# IO_Boardv3_281215.net
KiCad netlist of a schematic drawn in Altium Designer
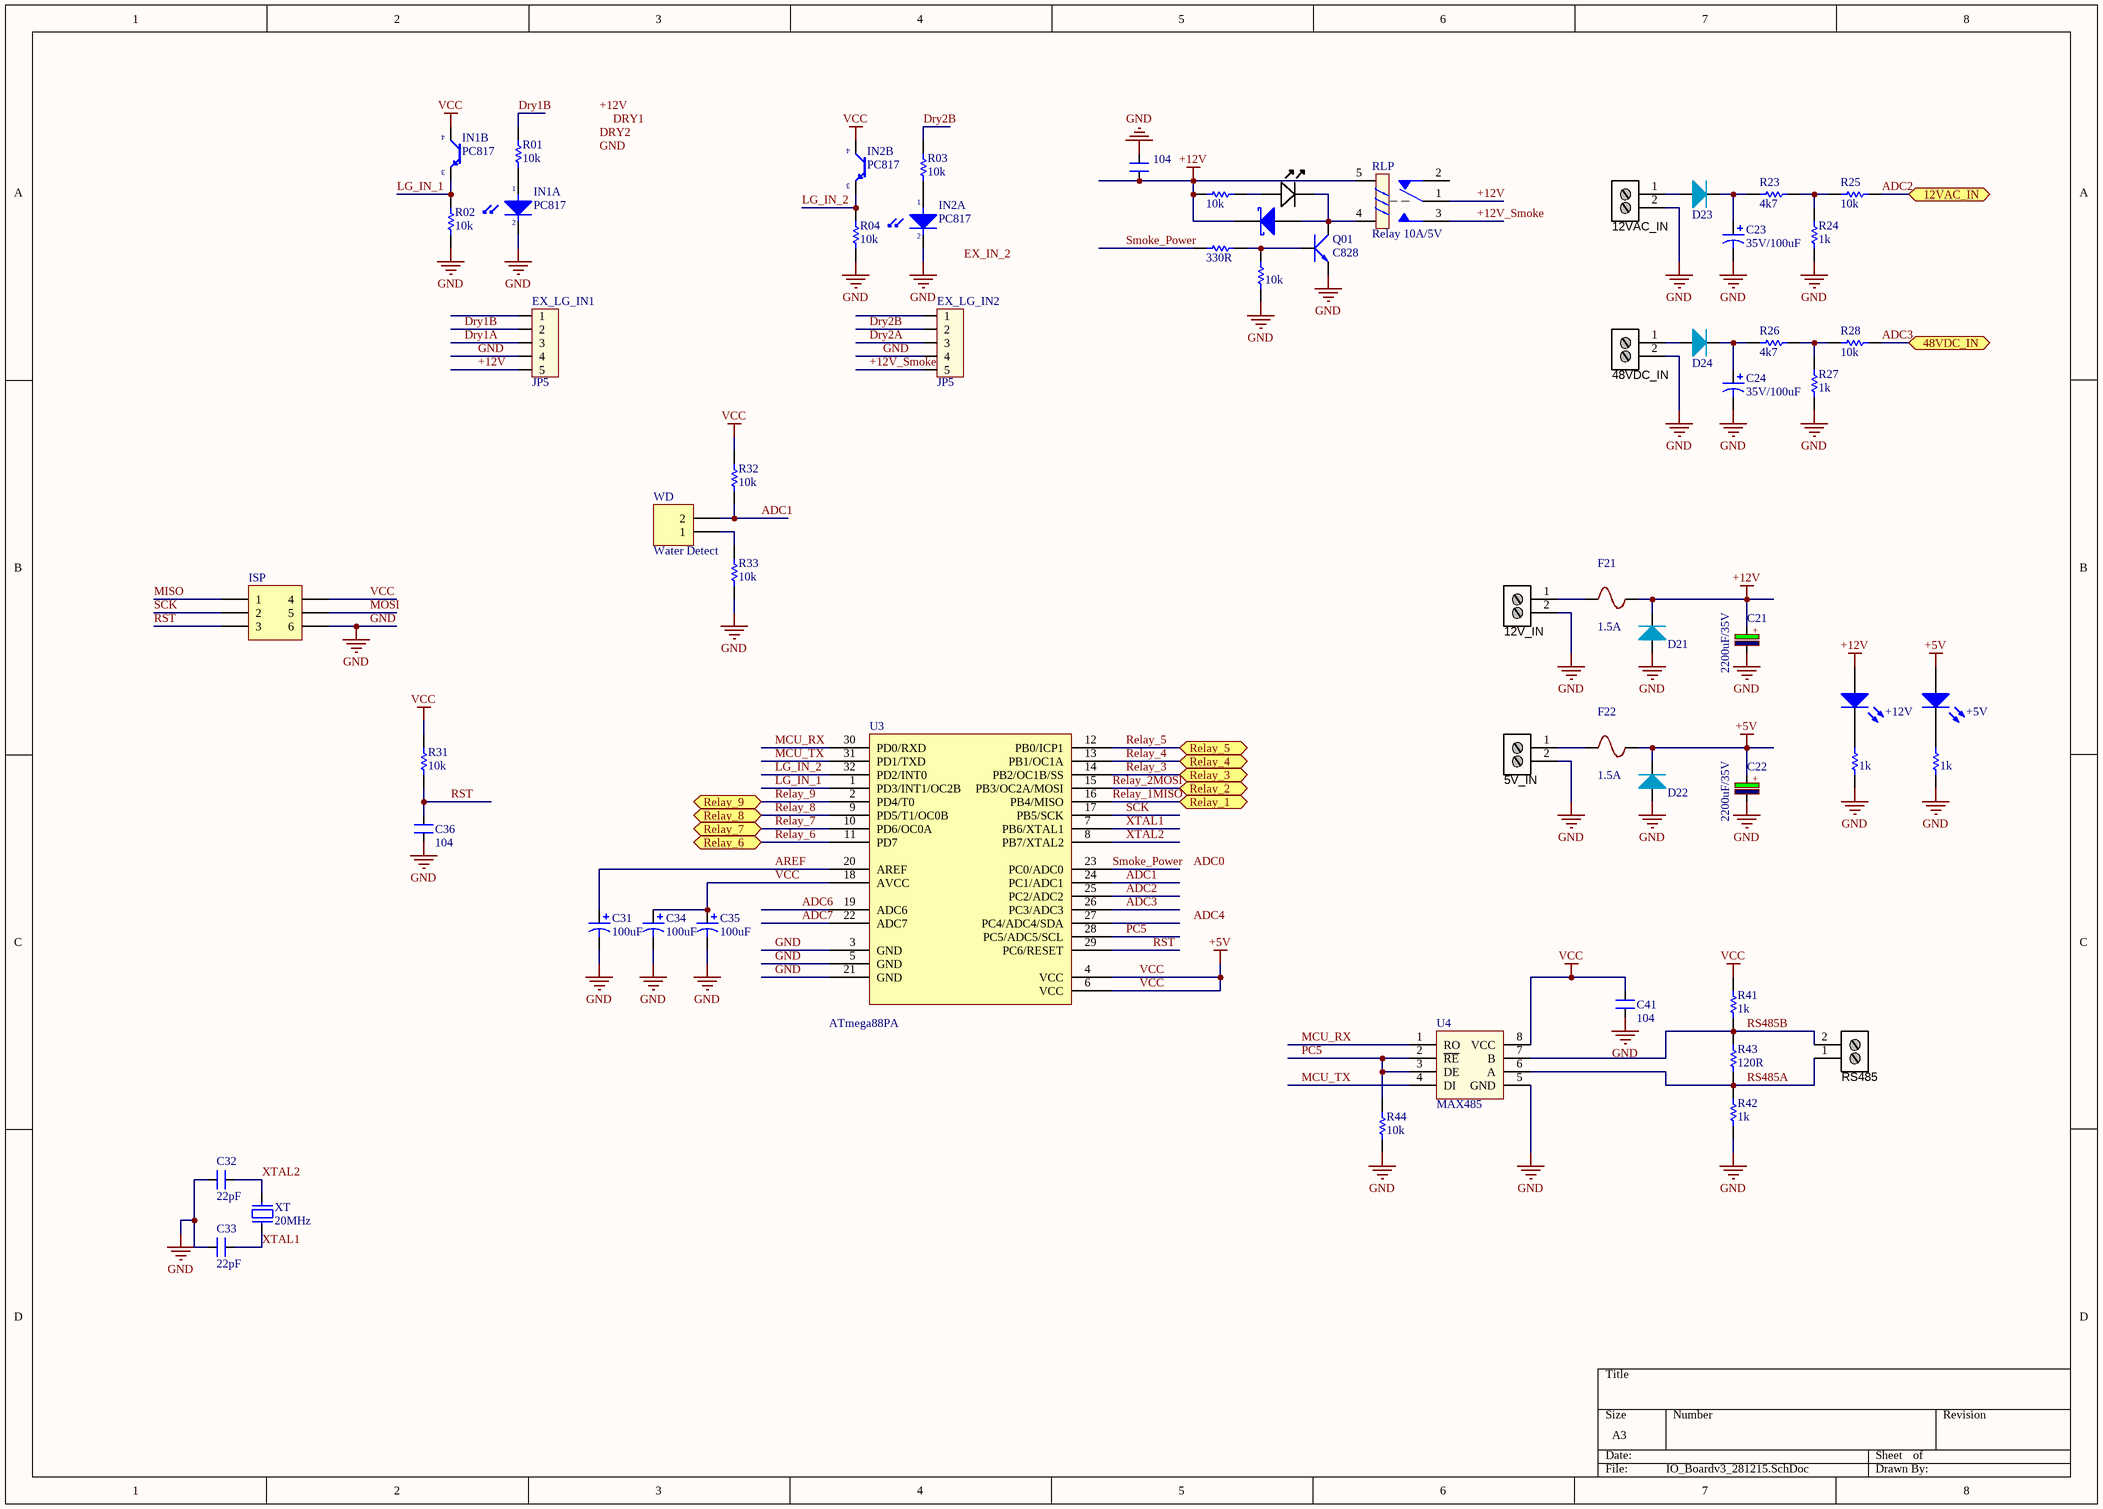
[diagram p0: IO_Boardv3_281215.SchDoc]

(export (version "E")
  (design (tool "Eeschema 10.0.6"))
  (components
    (comp (ref "+5V") (value "Led") (footprint "LED 5mm RED") (libsource (lib "Tuan") (part "Led")))
    (comp (ref "+12V") (value "Led") (footprint "LED 5mm RED") (libsource (lib "Tuan") (part "Led")))
    (comp (ref "5V_IN")
      (value "Stackable ScrewTerm")
      (footprint "2P_PCB_ScrewTerm_200mil")
      (description "Terminal Block Screw Type THT 2-Position 3.81mm pitch")
      (libsource (lib "PBL - Connectors") (part "2P_ScrewTerm_90S_3.81MM"))
    )
    (comp (ref "12VAC_IN")
      (value "Stackable ScrewTerm")
      (footprint "2P_PCB_ScrewTerm_200mil")
      (description "Terminal Block Screw Type THT 2-Position 3.81mm pitch")
      (libsource (lib "PBL - Connectors") (part "2P_ScrewTerm_90S_3.81MM"))
    )
    (comp (ref "12V_IN")
      (value "Stackable ScrewTerm")
      (footprint "2P_PCB_ScrewTerm_200mil")
      (description "Terminal Block Screw Type THT 2-Position 3.81mm pitch")
      (libsource (lib "PBL - Connectors") (part "2P_ScrewTerm_90S_3.81MM"))
    )
    (comp (ref "48VDC_IN")
      (value "Stackable ScrewTerm")
      (footprint "2P_PCB_ScrewTerm_200mil")
      (description "Terminal Block Screw Type THT 2-Position 3.81mm pitch")
      (libsource (lib "PBL - Connectors") (part "2P_ScrewTerm_90S_3.81MM"))
    )
    (comp (ref "C01")
      (value "104")
      (footprint "CAPC2012N_F")
      (fields (field (name "Comment") "CAP NP"))
      (libsource (lib "Tuan") (part "CAP NP"))
    )
    (comp (ref "C21")
      (value "2200uF/35V")
      (footprint "heromap:CP_1000uF_25V")
      (description "Cap 1000uF/16V - 220uF/50V")
      (libsource (lib "heromap") (part "CP4"))
    )
    (comp (ref "C22")
      (value "2200uF/35V")
      (footprint "heromap:CP_1000uF_25V")
      (description "Cap 1000uF/16V - 220uF/50V")
      (libsource (lib "heromap") (part "CP4"))
    )
    (comp (ref "C23")
      (value "35V/100uF")
      (footprint "CAP_ELEC_6.3x4.2")
      (fields (field (name "Comment") "Cap"))
      (libsource (lib "Tuan") (part "Cap"))
    )
    (comp (ref "C24")
      (value "35V/100uF")
      (footprint "CAP_ELEC_6.3x4.2")
      (fields (field (name "Comment") "Cap"))
      (libsource (lib "Tuan") (part "Cap"))
    )
    (comp (ref "C31")
      (value "100uF")
      (footprint "CAPC2012N_F")
      (fields (field (name "Comment") "Cap"))
      (libsource (lib "Tuan") (part "Cap"))
    )
    (comp (ref "C32")
      (value "22pF")
      (footprint "CAPC1608N")
      (fields (field (name "Comment") "CAP NP"))
      (libsource (lib "Tuan") (part "CAP NP"))
    )
    (comp (ref "C33")
      (value "22pF")
      (footprint "CAPC1608N")
      (fields (field (name "Comment") "CAP NP"))
      (libsource (lib "Tuan") (part "CAP NP"))
    )
    (comp (ref "C34")
      (value "100uF")
      (footprint "CAPC2012N_F")
      (fields (field (name "Comment") "Cap"))
      (libsource (lib "Tuan") (part "Cap"))
    )
    (comp (ref "C35")
      (value "100uF")
      (footprint "CAPC2012N_F")
      (fields (field (name "Comment") "Cap"))
      (libsource (lib "Tuan") (part "Cap"))
    )
    (comp (ref "C36")
      (value "104")
      (footprint "CAPC1608N")
      (fields (field (name "Comment") "CAP NP"))
      (libsource (lib "Tuan") (part "CAP NP"))
    )
    (comp (ref "C41")
      (value "104")
      (footprint "CAPC2012N_F")
      (fields (field (name "Comment") "100nF/104"))
      (libsource (lib "Tuan") (part "CAP NP"))
    )
    (comp (ref "D01") (value "Diode") (footprint "DO-214AC") (libsource (lib "") (part "Diode_1")))
    (comp (ref "D21") (value "Diode") (footprint "DO-214AC") (libsource (lib "Tuan") (part "Diode")))
    (comp (ref "D22") (value "Diode") (footprint "DO-214AC") (libsource (lib "Tuan") (part "Diode")))
    (comp (ref "D23") (value "Diode") (footprint "DO-214AC") (libsource (lib "Tuan") (part "Diode")))
    (comp (ref "D24") (value "Diode") (footprint "DO-214AC") (libsource (lib "Tuan") (part "Diode")))
    (comp (ref "E01")
      (value "Blue")
      (footprint "LED-0805-A")
      (description "LED 0805 SMD Blue 100mcd 470nm")
      (libsource (lib "PBL - Light Sources") (part "LED_SMD_Blue_0805_100mcd"))
    )
    (comp (ref "EX_LG_IN1")
      (value "JP5")
      (footprint "heromap:CON5")
      (description "Connector 5")
      (libsource (lib "heromap") (part "Con5"))
    )
    (comp (ref "EX_LG_IN2")
      (value "JP5")
      (footprint "heromap:CON5")
      (description "Connector 5")
      (libsource (lib "heromap") (part "Con5"))
    )
    (comp (ref "F21") (value "1.5A") (footprint "FUSE_SR-5-BK") (libsource (lib "Tuan") (part "Fuse")))
    (comp (ref "F22") (value "1.5A") (footprint "FUSE_SR-5-BK") (libsource (lib "Tuan") (part "Fuse")))
    (comp (ref "IN1") (value "PC817") (footprint "DIP4/W0.3") (libsource (lib "Tuan") (part "Opto")))
    (comp (ref "IN2") (value "PC817") (footprint "DIP4/W0.3") (libsource (lib "Tuan") (part "Opto")))
    (comp (ref "ISP")
      (value "Header 3X2A")
      (footprint "HDR2X3_CEN")
      (description "Header, 3-Pin, Dual row")
      (fields (field (name "PUBLISHER") "Altium Limited"))
      (libsource (lib "Miscellaneous Connectors") (part "Header 3X2A"))
    )
    (comp (ref "Q01")
      (value "C828")
      (footprint "SOT23 TOP")
      (description "Transistor C828 C1815....")
      (libsource (lib "Tuan") (part "NPN"))
    )
    (comp (ref "R01")
      (value "10k")
      (footprint "RESC2012N_F")
      (fields (field (name "Comment") "Res"))
      (libsource (lib "Tuan") (part "Res"))
    )
    (comp (ref "R02")
      (value "10k")
      (footprint "RESC2012N_F")
      (fields (field (name "Comment") "Res"))
      (libsource (lib "Tuan") (part "Res"))
    )
    (comp (ref "R03")
      (value "10k")
      (footprint "RESC2012N_F")
      (fields (field (name "Comment") "Res"))
      (libsource (lib "Tuan") (part "Res"))
    )
    (comp (ref "R04")
      (value "10k")
      (footprint "RESC2012N_F")
      (fields (field (name "Comment") "Res"))
      (libsource (lib "Tuan") (part "Res"))
    )
    (comp (ref "R05")
      (value "10k")
      (footprint "RESC1608N_ZERO")
      (fields (field (name "Comment") "Res"))
      (libsource (lib "Tuan") (part "Res"))
    )
    (comp (ref "R06")
      (value "10k")
      (footprint "RESC1608N_ZERO")
      (fields (field (name "Comment") "Res"))
      (libsource (lib "Tuan") (part "Res"))
    )
    (comp (ref "R07")
      (value "330R")
      (footprint "RESC1608N_ZERO")
      (fields (field (name "Comment") "Res"))
      (libsource (lib "Tuan") (part "Res"))
    )
    (comp (ref "R21")
      (value "1k")
      (footprint "RESC2012N_F")
      (fields (field (name "Comment") "Res_0805_1k"))
      (libsource (lib "Tuan") (part "Res"))
    )
    (comp (ref "R22")
      (value "1k")
      (footprint "RESC2012N_F")
      (fields (field (name "Comment") "Res_0805_1k"))
      (libsource (lib "Tuan") (part "Res"))
    )
    (comp (ref "R23")
      (value "4k7")
      (footprint "RESC2012N_F")
      (fields (field (name "Comment") "Res"))
      (libsource (lib "Tuan") (part "Res"))
    )
    (comp (ref "R24")
      (value "1k")
      (footprint "RESC2012N_F")
      (fields (field (name "Comment") "Res"))
      (libsource (lib "Tuan") (part "Res"))
    )
    (comp (ref "R25")
      (value "10k")
      (footprint "RESC2012N_F")
      (fields (field (name "Comment") "Res"))
      (libsource (lib "Tuan") (part "Res"))
    )
    (comp (ref "R26")
      (value "4k7")
      (footprint "RESC2012N_F")
      (fields (field (name "Comment") "Res"))
      (libsource (lib "Tuan") (part "Res"))
    )
    (comp (ref "R27")
      (value "1k")
      (footprint "RESC2012N_F")
      (fields (field (name "Comment") "Res"))
      (libsource (lib "Tuan") (part "Res"))
    )
    (comp (ref "R28")
      (value "10k")
      (footprint "RESC2012N_F")
      (fields (field (name "Comment") "Res"))
      (libsource (lib "Tuan") (part "Res"))
    )
    (comp (ref "R31")
      (value "10k")
      (footprint "RESC1608N_ZERO")
      (fields (field (name "Comment") "Res"))
      (libsource (lib "Tuan") (part "Res"))
    )
    (comp (ref "R32")
      (value "10k")
      (footprint "RESC2012N_F")
      (fields (field (name "Comment") "Res"))
      (libsource (lib "Tuan") (part "Res"))
    )
    (comp (ref "R33")
      (value "10k")
      (footprint "RESC2012N_F")
      (fields (field (name "Comment") "Res"))
      (libsource (lib "Tuan") (part "Res"))
    )
    (comp (ref "R41")
      (value "1k")
      (footprint "RESC2012N_F")
      (description "Tro dan")
      (libsource (lib "GPS_Clock_v12") (part "Res"))
    )
    (comp (ref "R42")
      (value "1k")
      (footprint "RESC2012N_F")
      (description "Tro dan")
      (libsource (lib "GPS_Clock_v12") (part "Res"))
    )
    (comp (ref "R43")
      (value "120R")
      (footprint "RESC2012N_F")
      (description "Tro dan")
      (fields (field (name "Comment") "330R"))
      (libsource (lib "GPS_Clock_v12") (part "Res"))
    )
    (comp (ref "R44")
      (value "10k")
      (footprint "RESC2012N_F")
      (description "Tro dan")
      (fields (field (name "Comment") "330R"))
      (libsource (lib "GPS_Clock_v12") (part "Res"))
    )
    (comp (ref "RLP")
      (value "Relay 10A/5V")
      (footprint "RL_5PIN")
      (description "Relay SPDT,10A - 12VDC 5 Pin")
      (libsource (lib "syhaunguyen") (part "Relay 1"))
    )
    (comp (ref "RS485")
      (value "Stackable ScrewTerm")
      (footprint "2P_PCB1")
      (description "Terminal Block Screw Type THT 2-Position 3.81mm pitch")
      (libsource (lib "") (part "2P_ScrewTerm_90S_3.81MM_1"))
    )
    (comp (ref "U3")
      (value "ATmega88PA")
      (footprint "32PIN")
      (description "ATmega48/168/328")
      (libsource (lib "Tuan") (part "ATmega48/168/328"))
    )
    (comp (ref "U4")
      (value "MAX485")
      (footprint "SO-8")
      (description "RS232 - RS485 (Same sn75176)")
      (libsource (lib "heromap") (part "MAX485"))
    )
    (comp (ref "WD")
      (value "Water Detect")
      (footprint "heromap:HDR1X2")
      (description "Header, 2-Pin")
      (fields (field (name "PUBLISHER") "Altium Limited"))
      (libsource (lib "heromap") (part "Header 2"))
    )
    (comp (ref "XT") (value "20MHz") (footprint "XT2") (libsource (lib "Tuan") (part "Crystal")))
  )
  (nets
    (net (code "1") (name "+5V") (class "Default")
      (node (ref "+5V") (pin "1") (pinfunction "A_1") (pintype "passive"))
      (node (ref "C22") (pin "1") (pinfunction "1_1") (pintype "passive"))
      (node (ref "C34") (pin "1") (pinfunction "1_1") (pintype "passive"))
      (node (ref "C35") (pin "1") (pinfunction "1_1") (pintype "passive"))
      (node (ref "C41") (pin "2") (pinfunction "2_2") (pintype "passive"))
      (node (ref "D22") (pin "2") (pinfunction "K_2") (pintype "passive"))
      (node (ref "F22") (pin "2") (pinfunction "2_2") (pintype "passive"))
      (node (ref "IN1") (pin "4") (pinfunction "C_4") (pintype "passive"))
      (node (ref "IN2") (pin "4") (pinfunction "C_4") (pintype "passive"))
      (node (ref "ISP") (pin "4") (pinfunction "4_4") (pintype "passive"))
      (node (ref "R31") (pin "2") (pinfunction "2_2") (pintype "passive"))
      (node (ref "R32") (pin "2") (pinfunction "2_2") (pintype "passive"))
      (node (ref "R41") (pin "2") (pinfunction "2_2") (pintype "passive"))
      (node (ref "U3") (pin "18") (pinfunction "AVCC_18") (pintype "passive"))
      (node (ref "U3") (pin "4") (pinfunction "VCC_4") (pintype "passive"))
      (node (ref "U3") (pin "6") (pinfunction "VCC_6") (pintype "passive"))
      (node (ref "U4") (pin "8") (pinfunction "VCC_8") (pintype "passive"))
    )
    (net (code "2") (name "+12V") (class "Default")
      (node (ref "+12V") (pin "1") (pinfunction "A_1") (pintype "passive"))
      (node (ref "C01") (pin "1") (pinfunction "1_1") (pintype "passive"))
      (node (ref "C21") (pin "1") (pinfunction "1_1") (pintype "passive"))
      (node (ref "D01") (pin "2") (pinfunction "K_2") (pintype "passive"))
      (node (ref "D21") (pin "2") (pinfunction "K_2") (pintype "passive"))
      (node (ref "EX_LG_IN1") (pin "5") (pinfunction "5_5") (pintype "passive"))
      (node (ref "F21") (pin "2") (pinfunction "2_2") (pintype "passive"))
      (node (ref "R05") (pin "2") (pinfunction "2_2") (pintype "passive"))
      (node (ref "RLP") (pin "1") (pinfunction "1_1") (pintype "passive"))
      (node (ref "RLP") (pin "5") (pinfunction "5_5") (pintype "passive"))
    )
    (net (code "3") (name "/+12V_Smoke") (class "Default")
      (node (ref "EX_LG_IN2") (pin "5") (pinfunction "5_5") (pintype "passive"))
      (node (ref "RLP") (pin "3") (pinfunction "3_3") (pintype "passive"))
    )
    (net (code "5") (name "/ADC1") (class "Default")
      (node (ref "R32") (pin "1") (pinfunction "1_1") (pintype "passive"))
      (node (ref "U3") (pin "24") (pinfunction "PC1/ADC1_24") (pintype "passive"))
      (node (ref "WD") (pin "2") (pinfunction "2_2") (pintype "passive"))
    )
    (net (code "6") (name "/ADC2") (class "Default")
      (node (ref "R25") (pin "2") (pinfunction "2_2") (pintype "passive"))
      (node (ref "U3") (pin "25") (pinfunction "PC2/ADC2_25") (pintype "passive"))
    )
    (net (code "7") (name "/ADC3") (class "Default")
      (node (ref "R28") (pin "2") (pinfunction "2_2") (pintype "passive"))
      (node (ref "U3") (pin "26") (pinfunction "PC3/ADC3_26") (pintype "passive"))
    )
    (net (code "9") (name "/ADC6") (class "Default")
      (node (ref "U3") (pin "19") (pinfunction "ADC6_19") (pintype "passive"))
    )
    (net (code "10") (name "/ADC7") (class "Default")
      (node (ref "U3") (pin "22") (pinfunction "ADC7_22") (pintype "passive"))
    )
    (net (code "11") (name "/AREF") (class "Default")
      (node (ref "C31") (pin "1") (pinfunction "1_1") (pintype "passive"))
      (node (ref "U3") (pin "20") (pinfunction "AREF_20") (pintype "passive"))
    )
    (net (code "14") (name "/Dry1A") (class "Default")
      (node (ref "EX_LG_IN1") (pin "3") (pinfunction "3_3") (pintype "passive"))
    )
    (net (code "15") (name "/Dry1B") (class "Default")
      (node (ref "EX_LG_IN1") (pin "2") (pinfunction "2_2") (pintype "passive"))
      (node (ref "R01") (pin "2") (pinfunction "2_2") (pintype "passive"))
    )
    (net (code "16") (name "/Dry2A") (class "Default")
      (node (ref "EX_LG_IN2") (pin "3") (pinfunction "3_3") (pintype "passive"))
    )
    (net (code "17") (name "/Dry2B") (class "Default")
      (node (ref "EX_LG_IN2") (pin "2") (pinfunction "2_2") (pintype "passive"))
      (node (ref "R03") (pin "2") (pinfunction "2_2") (pintype "passive"))
    )
    (net (code "19") (name "/LG_IN_1") (class "Default")
      (node (ref "IN1") (pin "3") (pinfunction "E_3") (pintype "passive"))
      (node (ref "R02") (pin "2") (pinfunction "2_2") (pintype "passive"))
      (node (ref "U3") (pin "1") (pinfunction "PD3/INT1/OC2B_1") (pintype "passive"))
    )
    (net (code "20") (name "/LG_IN_2") (class "Default")
      (node (ref "IN2") (pin "3") (pinfunction "E_3") (pintype "passive"))
      (node (ref "R04") (pin "2") (pinfunction "2_2") (pintype "passive"))
      (node (ref "U3") (pin "32") (pinfunction "PD2/INT0_32") (pintype "passive"))
    )
    (net (code "21") (name "/MCU_RX") (class "Default")
      (node (ref "U3") (pin "30") (pinfunction "PD0/RXD_30") (pintype "passive"))
      (node (ref "U4") (pin "1") (pinfunction "RO_1") (pintype "passive"))
    )
    (net (code "22") (name "/MCU_TX") (class "Default")
      (node (ref "U3") (pin "31") (pinfunction "PD1/TXD_31") (pintype "passive"))
      (node (ref "U4") (pin "4") (pinfunction "DI_4") (pintype "passive"))
    )
    (net (code "23") (name "/MISO") (class "Default")
      (node (ref "ISP") (pin "1") (pinfunction "1_1") (pintype "passive"))
      (node (ref "U3") (pin "16") (pinfunction "PB4/MISO_16") (pintype "passive"))
    )
    (net (code "24") (name "/MOSI") (class "Default")
      (node (ref "ISP") (pin "5") (pinfunction "5_5") (pintype "passive"))
      (node (ref "U3") (pin "15") (pinfunction "PB3/OC2A/MOSI_15") (pintype "passive"))
    )
    (net (code "25") (name "/PC5") (class "Default")
      (node (ref "R44") (pin "2") (pinfunction "2_2") (pintype "passive"))
      (node (ref "U3") (pin "28") (pinfunction "PC5/ADC5/SCL_28") (pintype "passive"))
      (node (ref "U4") (pin "2") (pinfunction "~{RE}_2") (pintype "passive"))
      (node (ref "U4") (pin "3") (pinfunction "DE_3") (pintype "passive"))
    )
    (net (code "26") (name "/RS485A") (class "Default")
      (node (ref "R42") (pin "2") (pinfunction "2_2") (pintype "passive"))
      (node (ref "R43") (pin "1") (pinfunction "1_1") (pintype "passive"))
      (node (ref "RS485") (pin "1") (pinfunction "1_1") (pintype "passive"))
      (node (ref "U4") (pin "6") (pinfunction "A_6") (pintype "passive"))
    )
    (net (code "27") (name "/RS485B") (class "Default")
      (node (ref "R41") (pin "1") (pinfunction "1_1") (pintype "passive"))
      (node (ref "R43") (pin "2") (pinfunction "2_2") (pintype "passive"))
      (node (ref "RS485") (pin "2") (pinfunction "2_2") (pintype "passive"))
      (node (ref "U4") (pin "7") (pinfunction "B_7") (pintype "passive"))
    )
    (net (code "28") (name "/RST") (class "Default")
      (node (ref "C36") (pin "2") (pinfunction "2_2") (pintype "passive"))
      (node (ref "ISP") (pin "3") (pinfunction "3_3") (pintype "passive"))
      (node (ref "R31") (pin "1") (pinfunction "1_1") (pintype "passive"))
      (node (ref "U3") (pin "29") (pinfunction "PC6/RESET_29") (pintype "passive"))
    )
    (net (code "29") (name "/Relay_3") (class "Default")
      (node (ref "U3") (pin "14") (pinfunction "PB2/OC1B/SS_14") (pintype "passive"))
    )
    (net (code "30") (name "/Relay_4") (class "Default")
      (node (ref "U3") (pin "13") (pinfunction "PB1/OC1A_13") (pintype "passive"))
    )
    (net (code "31") (name "/Relay_5") (class "Default")
      (node (ref "U3") (pin "12") (pinfunction "PB0/ICP1_12") (pintype "passive"))
    )
    (net (code "32") (name "/Relay_6") (class "Default")
      (node (ref "U3") (pin "11") (pinfunction "PD7_11") (pintype "passive"))
    )
    (net (code "33") (name "/Relay_7") (class "Default")
      (node (ref "U3") (pin "10") (pinfunction "PD6/OC0A_10") (pintype "passive"))
    )
    (net (code "34") (name "/Relay_8") (class "Default")
      (node (ref "U3") (pin "9") (pinfunction "PD5/T1/OC0B_9") (pintype "passive"))
    )
    (net (code "35") (name "/Relay_9") (class "Default")
      (node (ref "U3") (pin "2") (pinfunction "PD4/T0_2") (pintype "passive"))
    )
    (net (code "36") (name "/SCK") (class "Default")
      (node (ref "ISP") (pin "2") (pinfunction "2_2") (pintype "passive"))
      (node (ref "U3") (pin "17") (pinfunction "PB5/SCK_17") (pintype "passive"))
    )
    (net (code "37") (name "/Smoke_Power") (class "Default")
      (node (ref "R07") (pin "1") (pinfunction "1_1") (pintype "passive"))
      (node (ref "U3") (pin "23") (pinfunction "PC0/ADC0_23") (pintype "passive"))
    )
    (net (code "38") (name "/XTAL1") (class "Default")
      (node (ref "C33") (pin "1") (pinfunction "1_1") (pintype "passive"))
      (node (ref "U3") (pin "7") (pinfunction "PB6/XTAL1_7") (pintype "passive"))
      (node (ref "XT") (pin "1") (pinfunction "1_1") (pintype "passive"))
    )
    (net (code "39") (name "/XTAL2") (class "Default")
      (node (ref "C32") (pin "1") (pinfunction "1_1") (pintype "passive"))
      (node (ref "U3") (pin "8") (pinfunction "PB7/XTAL2_8") (pintype "passive"))
      (node (ref "XT") (pin "2") (pinfunction "2_2") (pintype "passive"))
    )
    (net (code "40") (name "GND") (class "Default")
      (node (ref "12VAC_IN") (pin "2") (pinfunction "2_2") (pintype "passive"))
      (node (ref "12V_IN") (pin "2") (pinfunction "2_2") (pintype "passive"))
      (node (ref "48VDC_IN") (pin "2") (pinfunction "2_2") (pintype "passive"))
      (node (ref "5V_IN") (pin "2") (pinfunction "2_2") (pintype "passive"))
      (node (ref "C01") (pin "2") (pinfunction "2_2") (pintype "passive"))
      (node (ref "C21") (pin "2") (pinfunction "2_2") (pintype "passive"))
      (node (ref "C22") (pin "2") (pinfunction "2_2") (pintype "passive"))
      (node (ref "C23") (pin "2") (pinfunction "2_2") (pintype "passive"))
      (node (ref "C24") (pin "2") (pinfunction "2_2") (pintype "passive"))
      (node (ref "C31") (pin "2") (pinfunction "2_2") (pintype "passive"))
      (node (ref "C32") (pin "2") (pinfunction "2_2") (pintype "passive"))
      (node (ref "C33") (pin "2") (pinfunction "2_2") (pintype "passive"))
      (node (ref "C34") (pin "2") (pinfunction "2_2") (pintype "passive"))
      (node (ref "C35") (pin "2") (pinfunction "2_2") (pintype "passive"))
      (node (ref "C36") (pin "1") (pinfunction "1_1") (pintype "passive"))
      (node (ref "C41") (pin "1") (pinfunction "1_1") (pintype "passive"))
      (node (ref "D21") (pin "1") (pinfunction "A_1") (pintype "passive"))
      (node (ref "D22") (pin "1") (pinfunction "A_1") (pintype "passive"))
      (node (ref "EX_LG_IN1") (pin "4") (pinfunction "4_4") (pintype "passive"))
      (node (ref "EX_LG_IN2") (pin "4") (pinfunction "4_4") (pintype "passive"))
      (node (ref "IN1") (pin "2") (pinfunction "K_2") (pintype "passive"))
      (node (ref "IN2") (pin "2") (pinfunction "K_2") (pintype "passive"))
      (node (ref "ISP") (pin "6") (pinfunction "6_6") (pintype "passive"))
      (node (ref "Q01") (pin "3") (pinfunction "E_3") (pintype "passive"))
      (node (ref "R02") (pin "1") (pinfunction "1_1") (pintype "passive"))
      (node (ref "R04") (pin "1") (pinfunction "1_1") (pintype "passive"))
      (node (ref "R06") (pin "1") (pinfunction "1_1") (pintype "passive"))
      (node (ref "R21") (pin "2") (pinfunction "2_2") (pintype "passive"))
      (node (ref "R22") (pin "2") (pinfunction "2_2") (pintype "passive"))
      (node (ref "R24") (pin "1") (pinfunction "1_1") (pintype "passive"))
      (node (ref "R27") (pin "1") (pinfunction "1_1") (pintype "passive"))
      (node (ref "R33") (pin "1") (pinfunction "1_1") (pintype "passive"))
      (node (ref "R42") (pin "1") (pinfunction "1_1") (pintype "passive"))
      (node (ref "R44") (pin "1") (pinfunction "1_1") (pintype "passive"))
      (node (ref "U3") (pin "21") (pinfunction "GND_21") (pintype "power_in"))
      (node (ref "U3") (pin "3") (pinfunction "GND_3") (pintype "power_in"))
      (node (ref "U3") (pin "5") (pinfunction "GND_5") (pintype "power_in"))
      (node (ref "U4") (pin "5") (pinfunction "GND_5") (pintype "passive"))
    )
    (net (code "41") (name "Net-(+5V-K)") (class "Default")
      (node (ref "+5V") (pin "2") (pinfunction "K_2") (pintype "passive"))
      (node (ref "R22") (pin "1") (pinfunction "1_1") (pintype "passive"))
    )
    (net (code "42") (name "Net-(+12V-K)") (class "Default")
      (node (ref "+12V") (pin "2") (pinfunction "K_2") (pintype "passive"))
      (node (ref "R21") (pin "1") (pinfunction "1_1") (pintype "passive"))
    )
    (net (code "43") (name "Net-(5V_IN-Pad1)") (class "Default")
      (node (ref "5V_IN") (pin "1") (pinfunction "1_1") (pintype "passive"))
      (node (ref "F22") (pin "1") (pinfunction "1_1") (pintype "passive"))
    )
    (net (code "44") (name "Net-(12V_IN-Pad1)") (class "Default")
      (node (ref "12V_IN") (pin "1") (pinfunction "1_1") (pintype "passive"))
      (node (ref "F21") (pin "1") (pinfunction "1_1") (pintype "passive"))
    )
    (net (code "45") (name "Net-(D01-A)") (class "Default")
      (node (ref "D01") (pin "1") (pinfunction "A_1") (pintype "passive"))
      (node (ref "E01") (pin "K") (pinfunction "K_K") (pintype "passive"))
      (node (ref "Q01") (pin "2") (pinfunction "C_2") (pintype "passive"))
      (node (ref "RLP") (pin "4") (pinfunction "4_4") (pintype "passive"))
    )
    (net (code "46") (name "Net-(D23-A)") (class "Default")
      (node (ref "12VAC_IN") (pin "1") (pinfunction "1_1") (pintype "passive"))
      (node (ref "D23") (pin "1") (pinfunction "A_1") (pintype "passive"))
    )
    (net (code "47") (name "Net-(D23-K)") (class "Default")
      (node (ref "C23") (pin "1") (pinfunction "1_1") (pintype "passive"))
      (node (ref "D23") (pin "2") (pinfunction "K_2") (pintype "passive"))
      (node (ref "R23") (pin "1") (pinfunction "1_1") (pintype "passive"))
    )
    (net (code "48") (name "Net-(D24-A)") (class "Default")
      (node (ref "48VDC_IN") (pin "1") (pinfunction "1_1") (pintype "passive"))
      (node (ref "D24") (pin "1") (pinfunction "A_1") (pintype "passive"))
    )
    (net (code "49") (name "Net-(D24-K)") (class "Default")
      (node (ref "C24") (pin "1") (pinfunction "1_1") (pintype "passive"))
      (node (ref "D24") (pin "2") (pinfunction "K_2") (pintype "passive"))
      (node (ref "R26") (pin "1") (pinfunction "1_1") (pintype "passive"))
    )
    (net (code "50") (name "Net-(E01-PadA)") (class "Default")
      (node (ref "E01") (pin "A") (pinfunction "A_A") (pintype "passive"))
      (node (ref "R05") (pin "1") (pinfunction "1_1") (pintype "passive"))
    )
    (net (code "51") (name "Net-(IN1A-A)") (class "Default")
      (node (ref "IN1") (pin "1") (pinfunction "A_1") (pintype "passive"))
      (node (ref "R01") (pin "1") (pinfunction "1_1") (pintype "passive"))
    )
    (net (code "52") (name "Net-(IN2A-A)") (class "Default")
      (node (ref "IN2") (pin "1") (pinfunction "A_1") (pintype "passive"))
      (node (ref "R03") (pin "1") (pinfunction "1_1") (pintype "passive"))
    )
    (net (code "53") (name "Net-(Q01-B)") (class "Default")
      (node (ref "Q01") (pin "1") (pinfunction "B_1") (pintype "passive"))
      (node (ref "R06") (pin "2") (pinfunction "2_2") (pintype "passive"))
      (node (ref "R07") (pin "2") (pinfunction "2_2") (pintype "passive"))
    )
    (net (code "54") (name "Net-(R23-Pad2)") (class "Default")
      (node (ref "R23") (pin "2") (pinfunction "2_2") (pintype "passive"))
      (node (ref "R24") (pin "2") (pinfunction "2_2") (pintype "passive"))
      (node (ref "R25") (pin "1") (pinfunction "1_1") (pintype "passive"))
    )
    (net (code "55") (name "Net-(R26-Pad2)") (class "Default")
      (node (ref "R26") (pin "2") (pinfunction "2_2") (pintype "passive"))
      (node (ref "R27") (pin "2") (pinfunction "2_2") (pintype "passive"))
      (node (ref "R28") (pin "1") (pinfunction "1_1") (pintype "passive"))
    )
    (net (code "56") (name "Net-(R33-Pad2)") (class "Default")
      (node (ref "R33") (pin "2") (pinfunction "2_2") (pintype "passive"))
      (node (ref "WD") (pin "1") (pinfunction "1_1") (pintype "passive"))
    )
    (net (code "57") (name "unconnected-(EX_LG_IN1-Pad1)") (class "Default")
      (node (ref "EX_LG_IN1") (pin "1") (pinfunction "1_1") (pintype "passive"))
    )
    (net (code "58") (name "unconnected-(EX_LG_IN2-Pad1)") (class "Default")
      (node (ref "EX_LG_IN2") (pin "1") (pinfunction "1_1") (pintype "passive"))
    )
    (net (code "59") (name "unconnected-(RLP-Pad2)") (class "Default")
      (node (ref "RLP") (pin "2") (pinfunction "2_2") (pintype "passive"))
    )
    (net (code "60") (name "unconnected-(U3-PC4{slash}ADC4{slash}SDA-Pad27)") (class "Default")
      (node (ref "U3") (pin "27") (pinfunction "PC4/ADC4/SDA_27") (pintype "passive"))
    )
  )
)
